# JTAG_POGOPIN_REV_A.net
KiCad netlist of a schematic drawn in Altium Designer
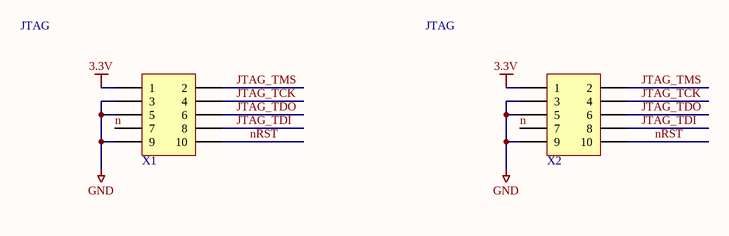
[diagram p0: JTAG_POGOPIN_REV_A.SchDoc]

(export (version "E")
  (design (tool "Eeschema 10.0.6"))
  (components
    (comp (ref "X1")
      (value "FCI male 2x5")
      (footprint "Connector:FCI header M2x5")
      (fields (field (name "MANUFACTURER") "FCI") (field (name "PART NUMBER") "20021121-00010C4LF"))
      (libsource (lib "Connector") (part "FCI male 2x5"))
    )
    (comp (ref "X2")
      (value "FCI male 2x5")
      (footprint "Connector:FCI header M2x5")
      (fields (field (name "MANUFACTURER") "FCI") (field (name "PART NUMBER") "20021121-00010C4LF"))
      (libsource (lib "Connector") (part "FCI male 2x5"))
    )
  )
  (nets
    (net (code "1") (name "/JTAG_TCK") (class "Default")
      (node (ref "X1") (pin "4") (pinfunction "4_4") (pintype "passive"))
      (node (ref "X2") (pin "4") (pinfunction "4_4") (pintype "passive"))
    )
    (net (code "2") (name "/JTAG_TDI") (class "Default")
      (node (ref "X1") (pin "8") (pinfunction "8_8") (pintype "passive"))
      (node (ref "X2") (pin "8") (pinfunction "8_8") (pintype "passive"))
    )
    (net (code "3") (name "/JTAG_TDO") (class "Default")
      (node (ref "X1") (pin "6") (pinfunction "6_6") (pintype "passive"))
      (node (ref "X2") (pin "6") (pinfunction "6_6") (pintype "passive"))
    )
    (net (code "4") (name "/JTAG_TMS") (class "Default")
      (node (ref "X1") (pin "2") (pinfunction "2_2") (pintype "passive"))
      (node (ref "X2") (pin "2") (pinfunction "2_2") (pintype "passive"))
    )
    (net (code "5") (name "/n") (class "Default")
      (node (ref "X1") (pin "7") (pinfunction "7_7") (pintype "passive"))
      (node (ref "X2") (pin "7") (pinfunction "7_7") (pintype "passive"))
    )
    (net (code "6") (name "/nRST") (class "Default")
      (node (ref "X1") (pin "10") (pinfunction "10_10") (pintype "passive"))
      (node (ref "X2") (pin "10") (pinfunction "10_10") (pintype "passive"))
    )
    (net (code "7") (name "3.3V") (class "Default")
      (node (ref "X1") (pin "1") (pinfunction "1_1") (pintype "passive"))
      (node (ref "X2") (pin "1") (pinfunction "1_1") (pintype "passive"))
    )
    (net (code "8") (name "GND") (class "Default")
      (node (ref "X1") (pin "3") (pinfunction "3_3") (pintype "passive"))
      (node (ref "X1") (pin "5") (pinfunction "5_5") (pintype "passive"))
      (node (ref "X1") (pin "9") (pinfunction "9_9") (pintype "passive"))
      (node (ref "X2") (pin "3") (pinfunction "3_3") (pintype "passive"))
      (node (ref "X2") (pin "5") (pinfunction "5_5") (pintype "passive"))
      (node (ref "X2") (pin "9") (pinfunction "9_9") (pintype "passive"))
    )
  )
)
